# RFE_Cellularv2.net
KiCad netlist of a schematic drawn in Altium Designer
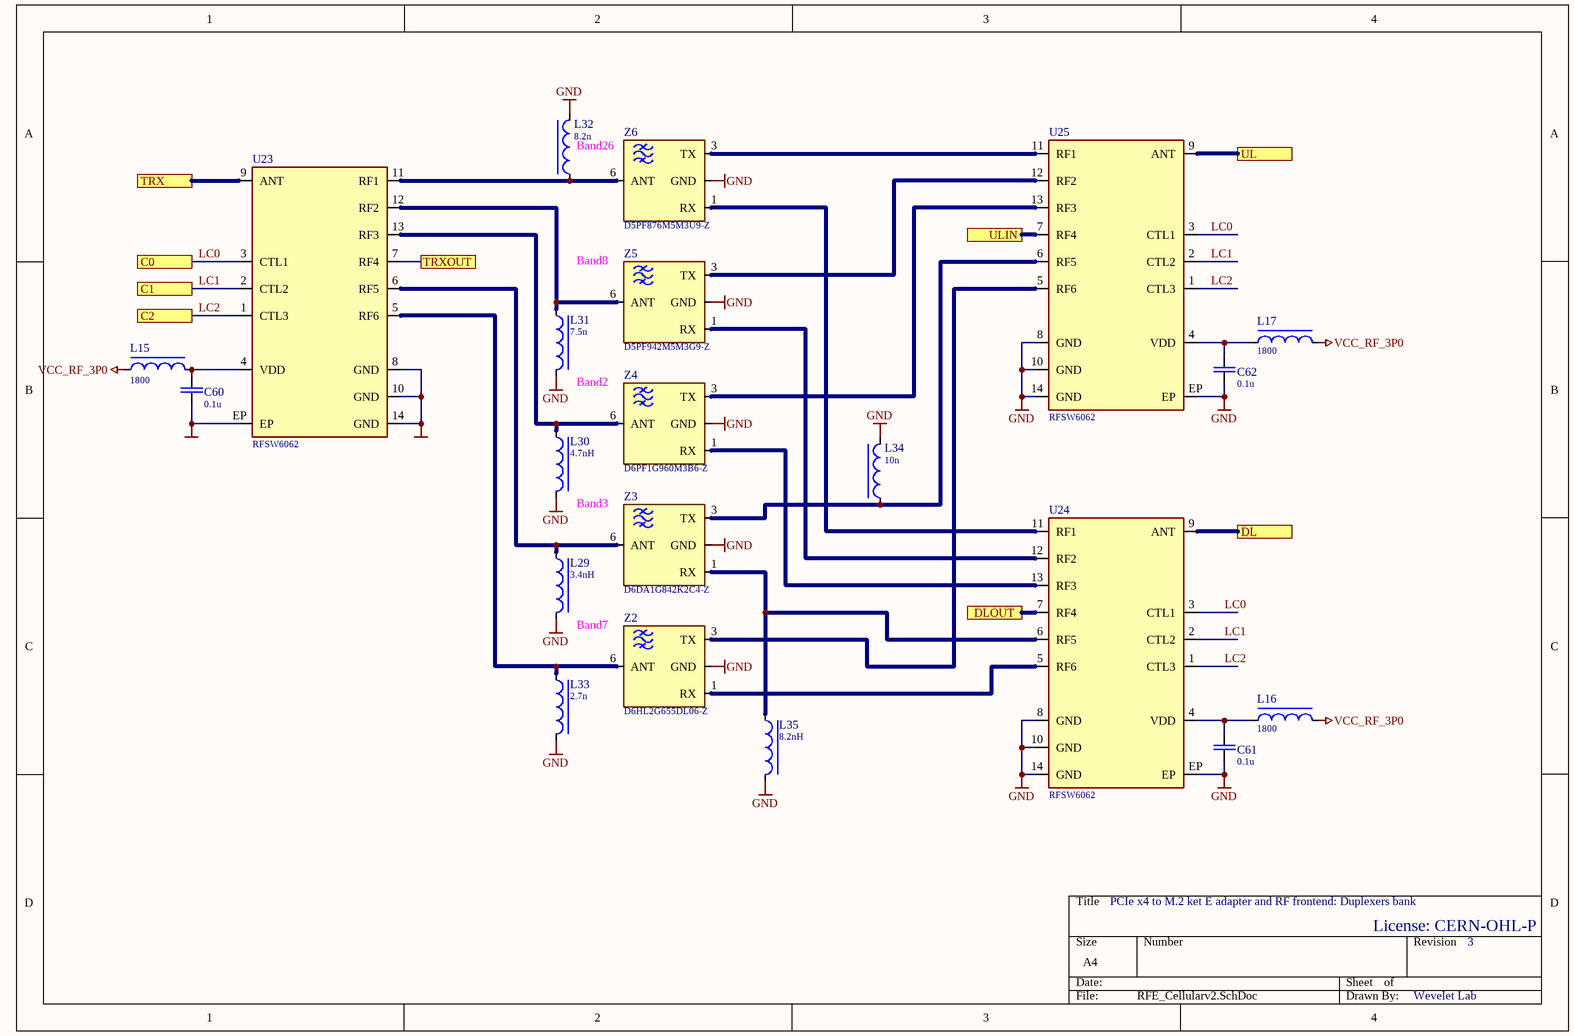
[diagram p0: RFE_Cellularv2.SchDoc]

(export (version "E")
  (design (tool "Eeschema 10.0.6"))
  (components
    (comp (ref "C60")
      (value "0.1u")
      (footprint "CAPC100X50X55L25N")
      (description "Capacitor, 0.1u, 25V, 10%, X7R, 0402")
      (fields
        (field (name "MANUFACTURER") "Murata Electronics")
        (field (name "Comment") "GRM155R71E104KE14D")
      )
      (libsource (lib "Capacitors") (part "GRM155R71E104KE14D"))
    )
    (comp (ref "C61")
      (value "0.1u")
      (footprint "CAPC100X50X55L25N")
      (description "Capacitor, 0.1u, 25V, 10%, X7R, 0402")
      (fields
        (field (name "MANUFACTURER") "Murata Electronics")
        (field (name "Comment") "GRM155R71E104KE14D")
      )
      (libsource (lib "Capacitors") (part "GRM155R71E104KE14D"))
    )
    (comp (ref "C62")
      (value "0.1u")
      (footprint "CAPC100X50X55L25N")
      (description "Capacitor, 0.1u, 25V, 10%, X7R, 0402")
      (fields
        (field (name "MANUFACTURER") "Murata Electronics")
        (field (name "Comment") "GRM155R71E104KE14D")
      )
      (libsource (lib "Capacitors") (part "GRM155R71E104KE14D"))
    )
    (comp (ref "L15")
      (value "1800")
      (footprint "INDC100X60X60L30N")
      (description "Ferrite bead, 1800Ohm@100MHz, 0,2A, 2.2Ohm, -55/+125, SMD0402")
      (fields (field (name "MANUFACTURER") "Murata Electronics") (field (name "Comment") "BLM15HD182SN1D"))
      (libsource (lib "") (part "BLM15HD182SN1D_1"))
    )
    (comp (ref "L16")
      (value "1800")
      (footprint "INDC100X60X60L30N")
      (description "Ferrite bead, 1800Ohm@100MHz, 0,2A, 2.2Ohm, -55/+125, SMD0402")
      (fields (field (name "MANUFACTURER") "Murata Electronics") (field (name "Comment") "BLM15HD182SN1D"))
      (libsource (lib "Inductor_Transformer") (part "BLM15HD182SN1D"))
    )
    (comp (ref "L17")
      (value "1800")
      (footprint "INDC100X60X60L30N")
      (description "Ferrite bead, 1800Ohm@100MHz, 0,2A, 2.2Ohm, -55/+125, SMD0402")
      (fields (field (name "MANUFACTURER") "Murata Electronics") (field (name "Comment") "BLM15HD182SN1D"))
      (libsource (lib "Inductor_Transformer") (part "BLM15HD182SN1D"))
    )
    (comp (ref "L29")
      (value "3.4nH")
      (footprint "INDC60X30X35L15N")
      (description "Inductor, 3.4n, -55/+125, SMD0201")
      (fields (field (name "MANUFACTURER") "TDK") (field (name "Comment") "MLG0603P3N4BT000"))
      (libsource (lib "Inductor_Transformer") (part "MLG0603P3N4BT000"))
    )
    (comp (ref "L30")
      (value "4.7nH")
      (footprint "INDC60X30X35L15N")
      (description "Inductor, 4.7n, -55/+125, SMD0201")
      (fields (field (name "MANUFACTURER") "TDK") (field (name "Comment") "MLG0603P4N7HT000"))
      (libsource (lib "Inductor_Transformer") (part "MLG0603P4N7HT000"))
    )
    (comp (ref "L31")
      (value "7.5n")
      (footprint "INDC60X30X35L15N")
      (description "Inductor, 7.5n, -55/+125, SMD0201")
      (fields (field (name "MANUFACTURER") "TDK") (field (name "Comment") "MLG0603P7N5HTD25"))
      (libsource (lib "Inductor_Transformer") (part "MLG0603P7N5HTD25"))
    )
    (comp (ref "L32")
      (value "8.2n")
      (footprint "INDC60X30X35L15N")
      (description "Inductor, 8.2n, -55/+125, SMD0201")
      (fields (field (name "MANUFACTURER") "TDK") (field (name "Comment") "MLG0603P8N2HTD25"))
      (libsource (lib "Inductor_Transformer") (part "MLG0603P8N2HTD25"))
    )
    (comp (ref "L33")
      (value "2.7n")
      (footprint "INDC60X30X35L15N")
      (description "Inductor, 2.7n, 0.5A, 200mOhm, -55/+125, SMD0201")
      (fields (field (name "MANUFACTURER") "TDK") (field (name "Comment") "MLG0603P2N7CTZ10"))
      (libsource (lib "Inductor_Transformer") (part "MLG0603P2N7CTZ10"))
    )
    (comp (ref "L34")
      (value "10n")
      (footprint "INDC60X30X35L15N")
      (description "Inductor, 10n, -55/+125, SMD0201")
      (fields (field (name "MANUFACTURER") "TDK") (field (name "Comment") "MLG0603P10NHTZ10"))
      (libsource (lib "Inductor_Transformer") (part "MLG0603P10NHTZ10"))
    )
    (comp (ref "L35")
      (value "8.2nH")
      (footprint "INDC60X30X35L15N")
      (description "Inductor, 8.2n, -55/+125, SMD0201")
      (fields (field (name "MANUFACTURER") "TDK") (field (name "Comment") "MLG0603P8N2HT000"))
      (libsource (lib "Inductor_Transformer") (part "MLG0603P8N2HT000"))
    )
    (comp (ref "U23")
      (value "RFSW6062")
      (footprint "QFN15P40_200X200X60L21X18T100N")
      (description "IC, Switch, SP6T, 5-6000MHz, -40/+85,  \r\n14-QFN")
      (fields (field (name "MANUFACTURER") "Qorvo"))
      (libsource (lib "") (part "RFSW6062_1"))
    )
    (comp (ref "U24")
      (value "RFSW6062")
      (footprint "QFN15P40_200X200X60L21X18T100N")
      (description "IC, Switch, SP6T, 5-6000MHz, -40/+85,  \r\n14-QFN")
      (fields (field (name "MANUFACTURER") "Qorvo"))
      (libsource (lib "IC Digital") (part "RFSW6062"))
    )
    (comp (ref "U25")
      (value "RFSW6062")
      (footprint "QFN15P40_200X200X60L21X18T100N")
      (description "IC, Switch, SP6T, 5-6000MHz, -40/+85,  \r\n14-QFN")
      (fields (field (name "MANUFACTURER") "Qorvo"))
      (libsource (lib "IC Digital") (part "RFSW6062"))
    )
    (comp (ref "Z2")
      (value "D6HL2G655DL06-Z")
      (footprint "TAIYO_YUDEN_SMD-9")
      (description "RF DUPLEXER, Band 7, -20/+85, SMD9")
      (fields (field (name "MANUFACTURER") "TAIYO YUDEN") (field (name "Comment") "D6HL2G655DL06"))
      (libsource (lib "Inductor_Transformer") (part "D6HL2G655DL06"))
    )
    (comp (ref "Z3")
      (value "D6DA1G842K2C4-Z")
      (footprint "TAIYO_YUDEN_SMD-8")
      (description "RF DUPLEXER, Band 3, -20/+85, SMD8")
      (fields (field (name "MANUFACTURER") "TAIYO YUDEN"))
      (libsource (lib "Inductor_Transformer") (part "D6DA1G842K2C4"))
    )
    (comp (ref "Z4")
      (value "D6PF1G960M3B6-Z")
      (footprint "TAIYO_YUDEN_SMD-9")
      (description "RF DUPLEXER, Band 2, -20/+85, SMD9")
      (fields (field (name "MANUFACTURER") "TAIYO YUDEN") (field (name "Comment") "D6PF1G960M3B6"))
      (libsource (lib "Inductor_Transformer") (part "D6PF1G960M3B6"))
    )
    (comp (ref "Z5")
      (value "D5PF942M5M3G9-Z")
      (footprint "TAIYO_YUDEN_SMD-9")
      (description "RF DUPLEXER, Band 8, -20/+85, SMD9")
      (fields (field (name "MANUFACTURER") "TAIYO YUDEN"))
      (libsource (lib "Inductor_Transformer") (part "D5PF942M5M3G9"))
    )
    (comp (ref "Z6")
      (value "D5PF876M5M3U9-Z")
      (footprint "TAIYO_YUDEN_SMD-9")
      (description "RF DUPLEXER, Band 26, -20/+85, SMD9")
      (fields (field (name "MANUFACTURER") "TAIYO YUDEN"))
      (libsource (lib "Inductor_Transformer") (part "D5PF876M5M3U9"))
    )
  )
  (nets
    (net (code "1") (name "/DL") (class "Default")
      (node (ref "U24") (pin "9") (pinfunction "ANT_9") (pintype "passive"))
    )
    (net (code "2") (name "/DLOUT") (class "Default")
      (node (ref "U24") (pin "7") (pinfunction "RF4_7") (pintype "passive"))
    )
    (net (code "3") (name "/LC0") (class "Default")
      (node (ref "U23") (pin "3") (pinfunction "CTL1_3") (pintype "passive"))
      (node (ref "U24") (pin "3") (pinfunction "CTL1_3") (pintype "passive"))
      (node (ref "U25") (pin "3") (pinfunction "CTL1_3") (pintype "passive"))
    )
    (net (code "4") (name "/LC1") (class "Default")
      (node (ref "U23") (pin "2") (pinfunction "CTL2_2") (pintype "passive"))
      (node (ref "U24") (pin "2") (pinfunction "CTL2_2") (pintype "passive"))
      (node (ref "U25") (pin "2") (pinfunction "CTL2_2") (pintype "passive"))
    )
    (net (code "5") (name "/LC2") (class "Default")
      (node (ref "U23") (pin "1") (pinfunction "CTL3_1") (pintype "passive"))
      (node (ref "U24") (pin "1") (pinfunction "CTL3_1") (pintype "passive"))
      (node (ref "U25") (pin "1") (pinfunction "CTL3_1") (pintype "passive"))
    )
    (net (code "6") (name "/TRX") (class "Default")
      (node (ref "U23") (pin "9") (pinfunction "ANT_9") (pintype "passive"))
    )
    (net (code "7") (name "/TRXOUT") (class "Default")
      (node (ref "U23") (pin "7") (pinfunction "RF4_7") (pintype "passive"))
    )
    (net (code "8") (name "/UL") (class "Default")
      (node (ref "U25") (pin "9") (pinfunction "ANT_9") (pintype "passive"))
    )
    (net (code "9") (name "/ULIN") (class "Default")
      (node (ref "U25") (pin "7") (pinfunction "RF4_7") (pintype "passive"))
    )
    (net (code "10") (name "GND") (class "Default")
      (node (ref "C60") (pin "2") (pinfunction "2_2") (pintype "passive"))
      (node (ref "C61") (pin "2") (pinfunction "2_2") (pintype "passive"))
      (node (ref "C62") (pin "2") (pinfunction "2_2") (pintype "passive"))
      (node (ref "L29") (pin "2") (pinfunction "2_2") (pintype "passive"))
      (node (ref "L30") (pin "2") (pinfunction "2_2") (pintype "passive"))
      (node (ref "L31") (pin "2") (pinfunction "2_2") (pintype "passive"))
      (node (ref "L32") (pin "2") (pinfunction "2_2") (pintype "passive"))
      (node (ref "L33") (pin "2") (pinfunction "2_2") (pintype "passive"))
      (node (ref "L34") (pin "2") (pinfunction "2_2") (pintype "passive"))
      (node (ref "L35") (pin "2") (pinfunction "2_2") (pintype "passive"))
      (node (ref "U23") (pin "10") (pinfunction "GND_10") (pintype "passive"))
      (node (ref "U23") (pin "14") (pinfunction "GND_14") (pintype "passive"))
      (node (ref "U23") (pin "8") (pinfunction "GND_8") (pintype "passive"))
      (node (ref "U23") (pin "EP") (pinfunction "EP_EP") (pintype "passive"))
      (node (ref "U24") (pin "10") (pinfunction "GND_10") (pintype "passive"))
      (node (ref "U24") (pin "14") (pinfunction "GND_14") (pintype "passive"))
      (node (ref "U24") (pin "8") (pinfunction "GND_8") (pintype "passive"))
      (node (ref "U24") (pin "EP") (pinfunction "EP_EP") (pintype "passive"))
      (node (ref "U25") (pin "10") (pinfunction "GND_10") (pintype "passive"))
      (node (ref "U25") (pin "14") (pinfunction "GND_14") (pintype "passive"))
      (node (ref "U25") (pin "8") (pinfunction "GND_8") (pintype "passive"))
      (node (ref "U25") (pin "EP") (pinfunction "EP_EP") (pintype "passive"))
      (node (ref "Z2") (pin "GND") (pinfunction "GND_GND") (pintype "passive"))
      (node (ref "Z3") (pin "GND") (pinfunction "GND_GND") (pintype "passive"))
      (node (ref "Z4") (pin "GND") (pinfunction "GND_GND") (pintype "passive"))
      (node (ref "Z5") (pin "GND") (pinfunction "GND_GND") (pintype "passive"))
      (node (ref "Z6") (pin "GND") (pinfunction "GND_GND") (pintype "passive"))
    )
    (net (code "11") (name "Net-(U23-RF1)") (class "Default")
      (node (ref "L32") (pin "1") (pinfunction "1_1") (pintype "passive"))
      (node (ref "U23") (pin "11") (pinfunction "RF1_11") (pintype "passive"))
      (node (ref "Z6") (pin "6") (pinfunction "ANT_6") (pintype "passive"))
    )
    (net (code "12") (name "Net-(U23-RF2)") (class "Default")
      (node (ref "L31") (pin "1") (pinfunction "1_1") (pintype "passive"))
      (node (ref "U23") (pin "12") (pinfunction "RF2_12") (pintype "passive"))
      (node (ref "Z5") (pin "6") (pinfunction "ANT_6") (pintype "passive"))
    )
    (net (code "13") (name "Net-(U23-RF3)") (class "Default")
      (node (ref "L30") (pin "1") (pinfunction "1_1") (pintype "passive"))
      (node (ref "U23") (pin "13") (pinfunction "RF3_13") (pintype "passive"))
      (node (ref "Z4") (pin "6") (pinfunction "ANT_6") (pintype "passive"))
    )
    (net (code "14") (name "Net-(U23-RF5)") (class "Default")
      (node (ref "L29") (pin "1") (pinfunction "1_1") (pintype "passive"))
      (node (ref "U23") (pin "6") (pinfunction "RF5_6") (pintype "passive"))
      (node (ref "Z3") (pin "6") (pinfunction "ANT_6") (pintype "passive"))
    )
    (net (code "15") (name "Net-(U23-RF6)") (class "Default")
      (node (ref "L33") (pin "1") (pinfunction "1_1") (pintype "passive"))
      (node (ref "U23") (pin "5") (pinfunction "RF6_5") (pintype "passive"))
      (node (ref "Z2") (pin "6") (pinfunction "ANT_6") (pintype "passive"))
    )
    (net (code "16") (name "Net-(U23-VDD)") (class "Default")
      (node (ref "C60") (pin "1") (pinfunction "1_1") (pintype "passive"))
      (node (ref "L15") (pin "1") (pinfunction "1_1") (pintype "passive"))
      (node (ref "U23") (pin "4") (pinfunction "VDD_4") (pintype "passive"))
    )
    (net (code "17") (name "Net-(U24-RF1)") (class "Default")
      (node (ref "U24") (pin "11") (pinfunction "RF1_11") (pintype "passive"))
      (node (ref "Z6") (pin "1") (pinfunction "RX_1") (pintype "passive"))
    )
    (net (code "18") (name "Net-(U24-RF2)") (class "Default")
      (node (ref "U24") (pin "12") (pinfunction "RF2_12") (pintype "passive"))
      (node (ref "Z5") (pin "1") (pinfunction "RX_1") (pintype "passive"))
    )
    (net (code "19") (name "Net-(U24-RF3)") (class "Default")
      (node (ref "U24") (pin "13") (pinfunction "RF3_13") (pintype "passive"))
      (node (ref "Z4") (pin "1") (pinfunction "RX_1") (pintype "passive"))
    )
    (net (code "20") (name "Net-(U24-RF5)") (class "Default")
      (node (ref "L35") (pin "1") (pinfunction "1_1") (pintype "passive"))
      (node (ref "U24") (pin "6") (pinfunction "RF5_6") (pintype "passive"))
      (node (ref "Z3") (pin "1") (pinfunction "RX_1") (pintype "passive"))
    )
    (net (code "21") (name "Net-(U24-RF6)") (class "Default")
      (node (ref "U24") (pin "5") (pinfunction "RF6_5") (pintype "passive"))
      (node (ref "Z2") (pin "1") (pinfunction "RX_1") (pintype "passive"))
    )
    (net (code "22") (name "Net-(U24-VDD)") (class "Default")
      (node (ref "C61") (pin "1") (pinfunction "1_1") (pintype "passive"))
      (node (ref "L16") (pin "1") (pinfunction "1_1") (pintype "passive"))
      (node (ref "U24") (pin "4") (pinfunction "VDD_4") (pintype "passive"))
    )
    (net (code "23") (name "Net-(U25-RF1)") (class "Default")
      (node (ref "U25") (pin "11") (pinfunction "RF1_11") (pintype "passive"))
      (node (ref "Z6") (pin "3") (pinfunction "TX_3") (pintype "passive"))
    )
    (net (code "24") (name "Net-(U25-RF2)") (class "Default")
      (node (ref "U25") (pin "12") (pinfunction "RF2_12") (pintype "passive"))
      (node (ref "Z5") (pin "3") (pinfunction "TX_3") (pintype "passive"))
    )
    (net (code "25") (name "Net-(U25-RF3)") (class "Default")
      (node (ref "U25") (pin "13") (pinfunction "RF3_13") (pintype "passive"))
      (node (ref "Z4") (pin "3") (pinfunction "TX_3") (pintype "passive"))
    )
    (net (code "26") (name "Net-(U25-RF5)") (class "Default")
      (node (ref "L34") (pin "1") (pinfunction "1_1") (pintype "passive"))
      (node (ref "U25") (pin "6") (pinfunction "RF5_6") (pintype "passive"))
      (node (ref "Z3") (pin "3") (pinfunction "TX_3") (pintype "passive"))
    )
    (net (code "27") (name "Net-(U25-RF6)") (class "Default")
      (node (ref "U25") (pin "5") (pinfunction "RF6_5") (pintype "passive"))
      (node (ref "Z2") (pin "3") (pinfunction "TX_3") (pintype "passive"))
    )
    (net (code "28") (name "Net-(U25-VDD)") (class "Default")
      (node (ref "C62") (pin "1") (pinfunction "1_1") (pintype "passive"))
      (node (ref "L17") (pin "1") (pinfunction "1_1") (pintype "passive"))
      (node (ref "U25") (pin "4") (pinfunction "VDD_4") (pintype "passive"))
    )
    (net (code "29") (name "VCC_RF_3P0") (class "Default")
      (node (ref "L15") (pin "2") (pinfunction "2_2") (pintype "passive"))
      (node (ref "L16") (pin "2") (pinfunction "2_2") (pintype "passive"))
      (node (ref "L17") (pin "2") (pinfunction "2_2") (pintype "passive"))
    )
  )
)
